# 7-segment.net
KiCad netlist of a schematic drawn in EAGLE
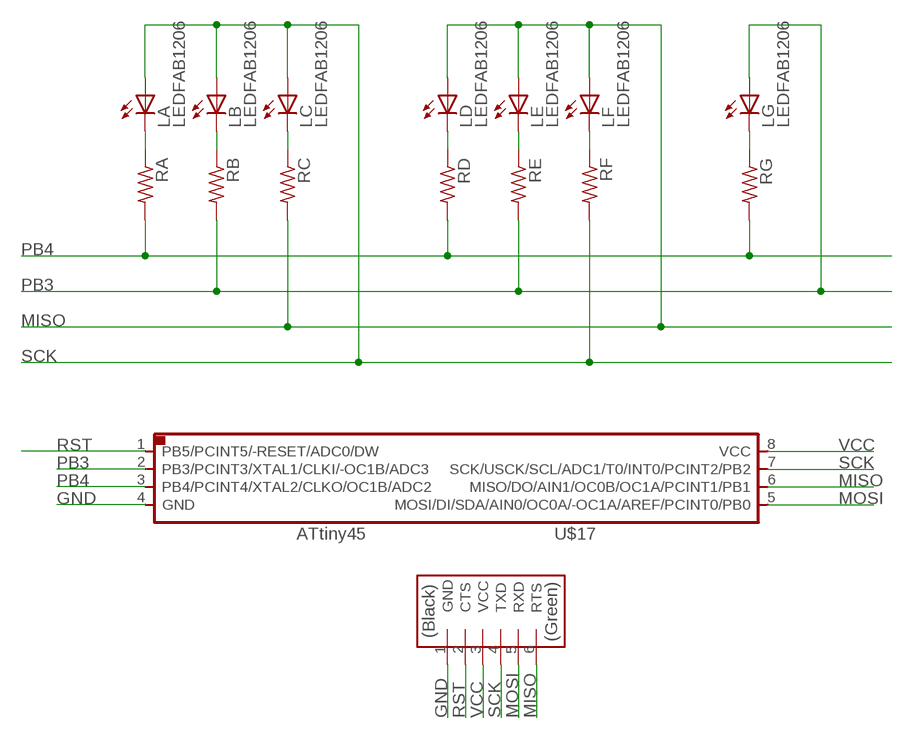
[diagram p0: schematic, sheet 1]

(export (version "E")
  (design (tool "Eeschema 10.0.6"))
  (components
    (comp (ref "LA")
      (value "LEDFAB1206")
      (footprint "eagle-import:LED1206FAB")
      (libsource (lib "eagle-import") (part "LEDFAB1206"))
    )
    (comp (ref "LB")
      (value "LEDFAB1206")
      (footprint "eagle-import:LED1206FAB")
      (libsource (lib "eagle-import") (part "LEDFAB1206"))
    )
    (comp (ref "LC")
      (value "LEDFAB1206")
      (footprint "eagle-import:LED1206FAB")
      (libsource (lib "eagle-import") (part "LEDFAB1206"))
    )
    (comp (ref "LD")
      (value "LEDFAB1206")
      (footprint "eagle-import:LED1206FAB")
      (libsource (lib "eagle-import") (part "LEDFAB1206"))
    )
    (comp (ref "LE")
      (value "LEDFAB1206")
      (footprint "eagle-import:LED1206FAB")
      (libsource (lib "eagle-import") (part "LEDFAB1206"))
    )
    (comp (ref "LF")
      (value "LEDFAB1206")
      (footprint "eagle-import:LED1206FAB")
      (libsource (lib "eagle-import") (part "LEDFAB1206"))
    )
    (comp (ref "LG")
      (value "LEDFAB1206")
      (footprint "eagle-import:LED1206FAB")
      (libsource (lib "eagle-import") (part "LEDFAB1206"))
    )
    (comp (ref "RA")
      (value "RES-US1206FAB")
      (footprint "eagle-import:R1206FAB")
      (libsource (lib "eagle-import") (part "RES-US1206FAB"))
    )
    (comp (ref "RB")
      (value "RES-US1206FAB")
      (footprint "eagle-import:R1206FAB")
      (libsource (lib "eagle-import") (part "RES-US1206FAB"))
    )
    (comp (ref "RC")
      (value "RES-US1206FAB")
      (footprint "eagle-import:R1206FAB")
      (libsource (lib "eagle-import") (part "RES-US1206FAB"))
    )
    (comp (ref "RD")
      (value "RES-US1206FAB")
      (footprint "eagle-import:R1206FAB")
      (libsource (lib "eagle-import") (part "RES-US1206FAB"))
    )
    (comp (ref "RE")
      (value "RES-US1206FAB")
      (footprint "eagle-import:R1206FAB")
      (libsource (lib "eagle-import") (part "RES-US1206FAB"))
    )
    (comp (ref "RF")
      (value "RES-US1206FAB")
      (footprint "eagle-import:R1206FAB")
      (libsource (lib "eagle-import") (part "RES-US1206FAB"))
    )
    (comp (ref "RG")
      (value "RES-US1206FAB")
      (footprint "eagle-import:R1206FAB")
      (libsource (lib "eagle-import") (part "RES-US1206FAB"))
    )
    (comp (ref "U$3")
      (value "FTDI-SMD-HEADER")
      (footprint "eagle-import:1X06SMD")
      (libsource (lib "eagle-import") (part "FTDI-SMD-HEADER"))
    )
    (comp (ref "U$17")
      (value "ATTINY45SI")
      (footprint "eagle-import:SOIC8")
      (libsource (lib "eagle-import") (part "ATTINY45SI"))
    )
  )
  (nets
    (net (code "1") (name "/GND") (class "Default")
      (node (ref "U$17") (pin "4") (pinfunction "GND_4") (pintype "bidirectional"))
      (node (ref "U$3") (pin "1") (pinfunction "GND_1") (pintype "bidirectional"))
    )
    (net (code "2") (name "/MISO") (class "Default")
      (node (ref "LD") (pin "1") (pinfunction "A_1") (pintype "passive"))
      (node (ref "LE") (pin "1") (pinfunction "A_1") (pintype "passive"))
      (node (ref "LF") (pin "1") (pinfunction "A_1") (pintype "passive"))
      (node (ref "RC") (pin "2") (pinfunction "2_2") (pintype "passive"))
      (node (ref "U$17") (pin "6") (pinfunction "MISO/DO/AIN1/OC0B/OC1A/PCINT1/PB1_6") (pintype "bidirectional"))
      (node (ref "U$3") (pin "6") (pinfunction "RTS_6") (pintype "bidirectional"))
    )
    (net (code "3") (name "/MOSI") (class "Default")
      (node (ref "U$17") (pin "5") (pinfunction "MOSI/DI/SDA/AIN0/OC0A/-OC1A/AREF/PCINT0/PB0_5") (pintype "bidirectional"))
      (node (ref "U$3") (pin "5") (pinfunction "RXD_5") (pintype "bidirectional"))
    )
    (net (code "4") (name "/PB3") (class "Default")
      (node (ref "LG") (pin "1") (pinfunction "A_1") (pintype "passive"))
      (node (ref "RB") (pin "2") (pinfunction "2_2") (pintype "passive"))
      (node (ref "RE") (pin "2") (pinfunction "2_2") (pintype "passive"))
      (node (ref "U$17") (pin "2") (pinfunction "PB3/PCINT3/XTAL1/CLKI/-OC1B/ADC3_2") (pintype "bidirectional"))
    )
    (net (code "5") (name "/PB4") (class "Default")
      (node (ref "RA") (pin "2") (pinfunction "2_2") (pintype "passive"))
      (node (ref "RD") (pin "2") (pinfunction "2_2") (pintype "passive"))
      (node (ref "RG") (pin "2") (pinfunction "2_2") (pintype "passive"))
      (node (ref "U$17") (pin "3") (pinfunction "PB4/PCINT4/XTAL2/CLKO/OC1B/ADC2_3") (pintype "bidirectional"))
    )
    (net (code "6") (name "/RST") (class "Default")
      (node (ref "U$17") (pin "1") (pinfunction "PB5/PCINT5/-RESET/ADC0/DW_1") (pintype "bidirectional"))
      (node (ref "U$3") (pin "2") (pinfunction "CTS_2") (pintype "bidirectional"))
    )
    (net (code "7") (name "/SCK") (class "Default")
      (node (ref "LA") (pin "1") (pinfunction "A_1") (pintype "passive"))
      (node (ref "LB") (pin "1") (pinfunction "A_1") (pintype "passive"))
      (node (ref "LC") (pin "1") (pinfunction "A_1") (pintype "passive"))
      (node (ref "RF") (pin "2") (pinfunction "2_2") (pintype "passive"))
      (node (ref "U$17") (pin "7") (pinfunction "SCK/USCK/SCL/ADC1/T0/INT0/PCINT2/PB2_7") (pintype "bidirectional"))
      (node (ref "U$3") (pin "4") (pinfunction "TXD_4") (pintype "bidirectional"))
    )
    (net (code "8") (name "/VCC") (class "Default")
      (node (ref "U$17") (pin "8") (pinfunction "VCC_8") (pintype "bidirectional"))
      (node (ref "U$3") (pin "3") (pinfunction "VCC_3") (pintype "bidirectional"))
    )
    (net (code "9") (name "Net-(LA-C)") (class "Default")
      (node (ref "LA") (pin "2") (pinfunction "C_2") (pintype "passive"))
      (node (ref "RA") (pin "1") (pinfunction "1_1") (pintype "passive"))
    )
    (net (code "10") (name "Net-(LB-C)") (class "Default")
      (node (ref "LB") (pin "2") (pinfunction "C_2") (pintype "passive"))
      (node (ref "RB") (pin "1") (pinfunction "1_1") (pintype "passive"))
    )
    (net (code "11") (name "Net-(LC-C)") (class "Default")
      (node (ref "LC") (pin "2") (pinfunction "C_2") (pintype "passive"))
      (node (ref "RC") (pin "1") (pinfunction "1_1") (pintype "passive"))
    )
    (net (code "12") (name "Net-(LD-C)") (class "Default")
      (node (ref "LD") (pin "2") (pinfunction "C_2") (pintype "passive"))
      (node (ref "RD") (pin "1") (pinfunction "1_1") (pintype "passive"))
    )
    (net (code "13") (name "Net-(LE-C)") (class "Default")
      (node (ref "LE") (pin "2") (pinfunction "C_2") (pintype "passive"))
      (node (ref "RE") (pin "1") (pinfunction "1_1") (pintype "passive"))
    )
    (net (code "14") (name "Net-(LF-C)") (class "Default")
      (node (ref "LF") (pin "2") (pinfunction "C_2") (pintype "passive"))
      (node (ref "RF") (pin "1") (pinfunction "1_1") (pintype "passive"))
    )
    (net (code "15") (name "Net-(LG-C)") (class "Default")
      (node (ref "LG") (pin "2") (pinfunction "C_2") (pintype "passive"))
      (node (ref "RG") (pin "1") (pinfunction "1_1") (pintype "passive"))
    )
  )
)
